# ehomeShades_doit_v2.net
KiCad netlist of a schematic drawn in EAGLE
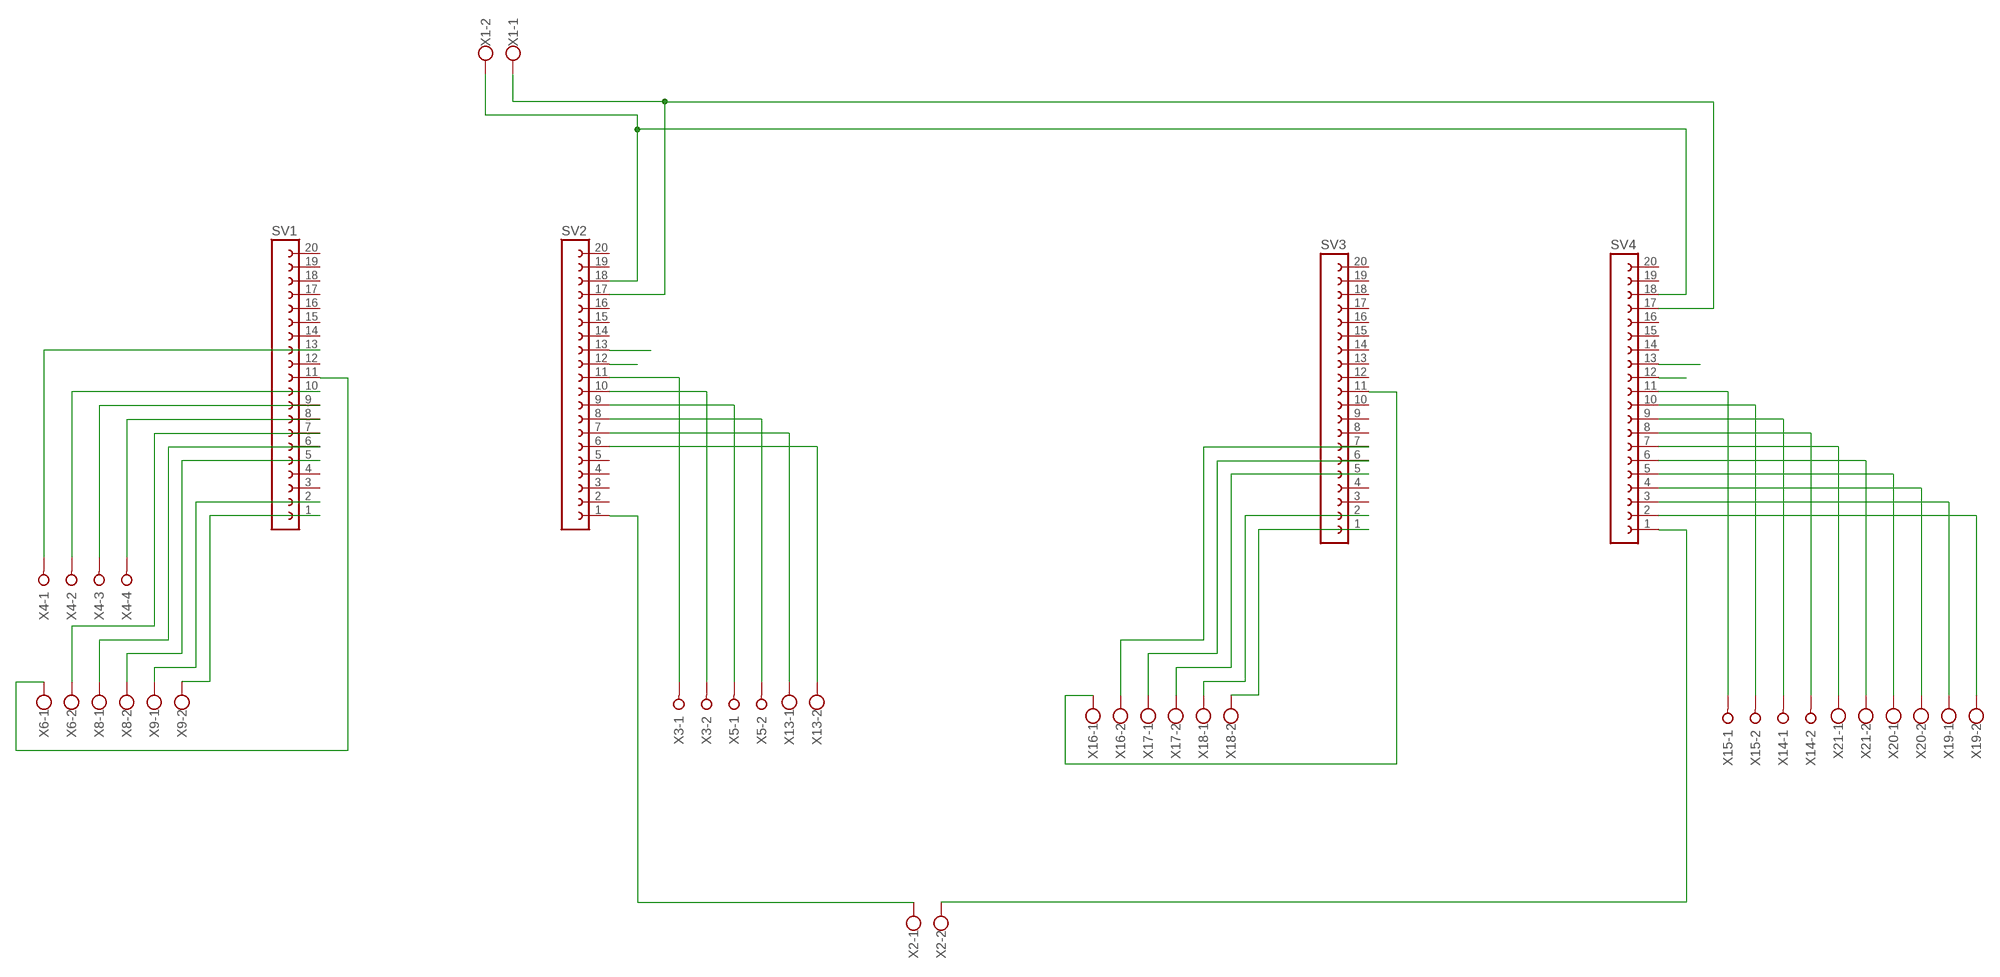
[diagram p0: schematic, sheet 1]

(export (version "E")
  (design (tool "Eeschema 10.0.6"))
  (components
    (comp (ref "SV1")
      (value "FE20-1")
      (footprint "eagle-import:FE20")
      (libsource (lib "eagle-import") (part "FE20-1"))
    )
    (comp (ref "SV2")
      (value "FE20-1")
      (footprint "eagle-import:FE20")
      (libsource (lib "eagle-import") (part "FE20-1"))
    )
    (comp (ref "SV3")
      (value "FE20-1")
      (footprint "eagle-import:FE20")
      (libsource (lib "eagle-import") (part "FE20-1"))
    )
    (comp (ref "SV4")
      (value "FE20-1")
      (footprint "eagle-import:FE20")
      (libsource (lib "eagle-import") (part "FE20-1"))
    )
    (comp (ref "X1")
      (value "W237-102")
      (footprint "eagle-import:W237-102")
      (fields (field (name "MPN") "237-102"))
      (libsource (lib "eagle-import") (part "W237-102"))
    )
    (comp (ref "X2")
      (value "W237-102")
      (footprint "eagle-import:W237-102")
      (fields (field (name "MPN") "237-102"))
      (libsource (lib "eagle-import") (part "W237-102"))
    )
    (comp (ref "X3")
      (value "W237-02P")
      (footprint "eagle-import:W237-132")
      (libsource (lib "eagle-import") (part "W237-02P"))
    )
    (comp (ref "X4")
      (value "W237-04P")
      (footprint "eagle-import:W237-4P")
      (libsource (lib "eagle-import") (part "W237-04P"))
    )
    (comp (ref "X5")
      (value "W237-02P")
      (footprint "eagle-import:W237-132")
      (libsource (lib "eagle-import") (part "W237-02P"))
    )
    (comp (ref "X6")
      (value "W237-102")
      (footprint "eagle-import:W237-102")
      (fields (field (name "MPN") "237-102"))
      (libsource (lib "eagle-import") (part "W237-102"))
    )
    (comp (ref "X8")
      (value "W237-102")
      (footprint "eagle-import:W237-102")
      (fields (field (name "MPN") "237-102"))
      (libsource (lib "eagle-import") (part "W237-102"))
    )
    (comp (ref "X9")
      (value "W237-102")
      (footprint "eagle-import:W237-102")
      (fields (field (name "MPN") "237-102"))
      (libsource (lib "eagle-import") (part "W237-102"))
    )
    (comp (ref "X13")
      (value "W237-102")
      (footprint "eagle-import:W237-102")
      (fields (field (name "MPN") "237-102"))
      (libsource (lib "eagle-import") (part "W237-102"))
    )
    (comp (ref "X14")
      (value "W237-02P")
      (footprint "eagle-import:W237-132")
      (libsource (lib "eagle-import") (part "W237-02P"))
    )
    (comp (ref "X15")
      (value "W237-02P")
      (footprint "eagle-import:W237-132")
      (libsource (lib "eagle-import") (part "W237-02P"))
    )
    (comp (ref "X16")
      (value "W237-102")
      (footprint "eagle-import:W237-102")
      (fields (field (name "MPN") "237-102"))
      (libsource (lib "eagle-import") (part "W237-102"))
    )
    (comp (ref "X17")
      (value "W237-102")
      (footprint "eagle-import:W237-102")
      (fields (field (name "MPN") "237-102"))
      (libsource (lib "eagle-import") (part "W237-102"))
    )
    (comp (ref "X18")
      (value "W237-102")
      (footprint "eagle-import:W237-102")
      (fields (field (name "MPN") "237-102"))
      (libsource (lib "eagle-import") (part "W237-102"))
    )
    (comp (ref "X19")
      (value "W237-102")
      (footprint "eagle-import:W237-102")
      (fields (field (name "MPN") "237-102"))
      (libsource (lib "eagle-import") (part "W237-102"))
    )
    (comp (ref "X20")
      (value "W237-102")
      (footprint "eagle-import:W237-102")
      (fields (field (name "MPN") "237-102"))
      (libsource (lib "eagle-import") (part "W237-102"))
    )
    (comp (ref "X21")
      (value "W237-102")
      (footprint "eagle-import:W237-102")
      (fields (field (name "MPN") "237-102"))
      (libsource (lib "eagle-import") (part "W237-102"))
    )
  )
  (nets
    (net (code "1") (name "Net-(X1A-KL)") (class "Default")
      (node (ref "SV2") (pin "17") (pinfunction "17_17") (pintype "passive"))
      (node (ref "SV4") (pin "17") (pinfunction "17_17") (pintype "passive"))
      (node (ref "X1") (pin "1") (pinfunction "KL_1") (pintype "passive"))
    )
    (net (code "2") (name "Net-(X1B-KL)") (class "Default")
      (node (ref "SV2") (pin "18") (pinfunction "18_18") (pintype "passive"))
      (node (ref "SV4") (pin "18") (pinfunction "18_18") (pintype "passive"))
      (node (ref "X1") (pin "2") (pinfunction "KL_2") (pintype "passive"))
    )
    (net (code "3") (name "Net-(X2A-KL)") (class "Default")
      (node (ref "SV2") (pin "1") (pinfunction "1_1") (pintype "passive"))
      (node (ref "X2") (pin "1") (pinfunction "KL_1") (pintype "passive"))
    )
    (net (code "4") (name "Net-(X2B-KL)") (class "Default")
      (node (ref "SV4") (pin "1") (pinfunction "1_1") (pintype "passive"))
      (node (ref "X2") (pin "2") (pinfunction "KL_2") (pintype "passive"))
    )
    (net (code "5") (name "Net-(X3A-KL)") (class "Default")
      (node (ref "SV2") (pin "11") (pinfunction "11_11") (pintype "passive"))
      (node (ref "X3") (pin "1") (pinfunction "KL_1") (pintype "passive"))
    )
    (net (code "6") (name "Net-(X3B-KL)") (class "Default")
      (node (ref "SV2") (pin "10") (pinfunction "10_10") (pintype "passive"))
      (node (ref "X3") (pin "2") (pinfunction "KL_2") (pintype "passive"))
    )
    (net (code "7") (name "Net-(X4A-KL)") (class "Default")
      (node (ref "SV1") (pin "13") (pinfunction "13_13") (pintype "passive"))
      (node (ref "X4") (pin "1") (pinfunction "KL_1") (pintype "passive"))
    )
    (net (code "8") (name "Net-(X4B-KL)") (class "Default")
      (node (ref "SV1") (pin "10") (pinfunction "10_10") (pintype "passive"))
      (node (ref "X4") (pin "2") (pinfunction "KL_2") (pintype "passive"))
    )
    (net (code "9") (name "Net-(X4C-KL)") (class "Default")
      (node (ref "SV1") (pin "9") (pinfunction "9_9") (pintype "passive"))
      (node (ref "X4") (pin "3") (pinfunction "KL_3") (pintype "passive"))
    )
    (net (code "10") (name "Net-(X4D-KL)") (class "Default")
      (node (ref "SV1") (pin "8") (pinfunction "8_8") (pintype "passive"))
      (node (ref "X4") (pin "4") (pinfunction "KL_4") (pintype "passive"))
    )
    (net (code "11") (name "Net-(X5A-KL)") (class "Default")
      (node (ref "SV2") (pin "9") (pinfunction "9_9") (pintype "passive"))
      (node (ref "X5") (pin "1") (pinfunction "KL_1") (pintype "passive"))
    )
    (net (code "12") (name "Net-(X5B-KL)") (class "Default")
      (node (ref "SV2") (pin "8") (pinfunction "8_8") (pintype "passive"))
      (node (ref "X5") (pin "2") (pinfunction "KL_2") (pintype "passive"))
    )
    (net (code "13") (name "Net-(X6A-KL)") (class "Default")
      (node (ref "SV1") (pin "11") (pinfunction "11_11") (pintype "passive"))
      (node (ref "X6") (pin "1") (pinfunction "KL_1") (pintype "passive"))
    )
    (net (code "14") (name "Net-(X6B-KL)") (class "Default")
      (node (ref "SV1") (pin "7") (pinfunction "7_7") (pintype "passive"))
      (node (ref "X6") (pin "2") (pinfunction "KL_2") (pintype "passive"))
    )
    (net (code "15") (name "Net-(X8A-KL)") (class "Default")
      (node (ref "SV1") (pin "6") (pinfunction "6_6") (pintype "passive"))
      (node (ref "X8") (pin "1") (pinfunction "KL_1") (pintype "passive"))
    )
    (net (code "16") (name "Net-(X8B-KL)") (class "Default")
      (node (ref "SV1") (pin "5") (pinfunction "5_5") (pintype "passive"))
      (node (ref "X8") (pin "2") (pinfunction "KL_2") (pintype "passive"))
    )
    (net (code "17") (name "Net-(X9A-KL)") (class "Default")
      (node (ref "SV1") (pin "2") (pinfunction "2_2") (pintype "passive"))
      (node (ref "X9") (pin "1") (pinfunction "KL_1") (pintype "passive"))
    )
    (net (code "18") (name "Net-(X9B-KL)") (class "Default")
      (node (ref "SV1") (pin "1") (pinfunction "1_1") (pintype "passive"))
      (node (ref "X9") (pin "2") (pinfunction "KL_2") (pintype "passive"))
    )
    (net (code "19") (name "Net-(X13A-KL)") (class "Default")
      (node (ref "SV2") (pin "7") (pinfunction "7_7") (pintype "passive"))
      (node (ref "X13") (pin "1") (pinfunction "KL_1") (pintype "passive"))
    )
    (net (code "20") (name "Net-(X13B-KL)") (class "Default")
      (node (ref "SV2") (pin "6") (pinfunction "6_6") (pintype "passive"))
      (node (ref "X13") (pin "2") (pinfunction "KL_2") (pintype "passive"))
    )
    (net (code "21") (name "Net-(X14A-KL)") (class "Default")
      (node (ref "SV4") (pin "9") (pinfunction "9_9") (pintype "passive"))
      (node (ref "X14") (pin "1") (pinfunction "KL_1") (pintype "passive"))
    )
    (net (code "22") (name "Net-(X14B-KL)") (class "Default")
      (node (ref "SV4") (pin "8") (pinfunction "8_8") (pintype "passive"))
      (node (ref "X14") (pin "2") (pinfunction "KL_2") (pintype "passive"))
    )
    (net (code "23") (name "Net-(X15A-KL)") (class "Default")
      (node (ref "SV4") (pin "11") (pinfunction "11_11") (pintype "passive"))
      (node (ref "X15") (pin "1") (pinfunction "KL_1") (pintype "passive"))
    )
    (net (code "24") (name "Net-(X15B-KL)") (class "Default")
      (node (ref "SV4") (pin "10") (pinfunction "10_10") (pintype "passive"))
      (node (ref "X15") (pin "2") (pinfunction "KL_2") (pintype "passive"))
    )
    (net (code "25") (name "Net-(X16A-KL)") (class "Default")
      (node (ref "SV3") (pin "11") (pinfunction "11_11") (pintype "passive"))
      (node (ref "X16") (pin "1") (pinfunction "KL_1") (pintype "passive"))
    )
    (net (code "26") (name "Net-(X16B-KL)") (class "Default")
      (node (ref "SV3") (pin "7") (pinfunction "7_7") (pintype "passive"))
      (node (ref "X16") (pin "2") (pinfunction "KL_2") (pintype "passive"))
    )
    (net (code "27") (name "Net-(X17A-KL)") (class "Default")
      (node (ref "SV3") (pin "6") (pinfunction "6_6") (pintype "passive"))
      (node (ref "X17") (pin "1") (pinfunction "KL_1") (pintype "passive"))
    )
    (net (code "28") (name "Net-(X17B-KL)") (class "Default")
      (node (ref "SV3") (pin "5") (pinfunction "5_5") (pintype "passive"))
      (node (ref "X17") (pin "2") (pinfunction "KL_2") (pintype "passive"))
    )
    (net (code "29") (name "Net-(X18A-KL)") (class "Default")
      (node (ref "SV3") (pin "2") (pinfunction "2_2") (pintype "passive"))
      (node (ref "X18") (pin "1") (pinfunction "KL_1") (pintype "passive"))
    )
    (net (code "30") (name "Net-(X18B-KL)") (class "Default")
      (node (ref "SV3") (pin "1") (pinfunction "1_1") (pintype "passive"))
      (node (ref "X18") (pin "2") (pinfunction "KL_2") (pintype "passive"))
    )
    (net (code "31") (name "Net-(X19A-KL)") (class "Default")
      (node (ref "SV4") (pin "3") (pinfunction "3_3") (pintype "passive"))
      (node (ref "X19") (pin "1") (pinfunction "KL_1") (pintype "passive"))
    )
    (net (code "32") (name "Net-(X19B-KL)") (class "Default")
      (node (ref "SV4") (pin "2") (pinfunction "2_2") (pintype "passive"))
      (node (ref "X19") (pin "2") (pinfunction "KL_2") (pintype "passive"))
    )
    (net (code "33") (name "Net-(X20A-KL)") (class "Default")
      (node (ref "SV4") (pin "5") (pinfunction "5_5") (pintype "passive"))
      (node (ref "X20") (pin "1") (pinfunction "KL_1") (pintype "passive"))
    )
    (net (code "34") (name "Net-(X20B-KL)") (class "Default")
      (node (ref "SV4") (pin "4") (pinfunction "4_4") (pintype "passive"))
      (node (ref "X20") (pin "2") (pinfunction "KL_2") (pintype "passive"))
    )
    (net (code "35") (name "Net-(X21A-KL)") (class "Default")
      (node (ref "SV4") (pin "7") (pinfunction "7_7") (pintype "passive"))
      (node (ref "X21") (pin "1") (pinfunction "KL_1") (pintype "passive"))
    )
    (net (code "36") (name "Net-(X21B-KL)") (class "Default")
      (node (ref "SV4") (pin "6") (pinfunction "6_6") (pintype "passive"))
      (node (ref "X21") (pin "2") (pinfunction "KL_2") (pintype "passive"))
    )
    (net (code "37") (name "unconnected-(SV1-Pad3)") (class "Default")
      (node (ref "SV1") (pin "3") (pinfunction "3_3") (pintype "passive"))
    )
    (net (code "38") (name "unconnected-(SV1-Pad4)") (class "Default")
      (node (ref "SV1") (pin "4") (pinfunction "4_4") (pintype "passive"))
    )
    (net (code "39") (name "unconnected-(SV1-Pad12)") (class "Default")
      (node (ref "SV1") (pin "12") (pinfunction "12_12") (pintype "passive"))
    )
    (net (code "40") (name "unconnected-(SV1-Pad14)") (class "Default")
      (node (ref "SV1") (pin "14") (pinfunction "14_14") (pintype "passive"))
    )
    (net (code "41") (name "unconnected-(SV1-Pad15)") (class "Default")
      (node (ref "SV1") (pin "15") (pinfunction "15_15") (pintype "passive"))
    )
    (net (code "42") (name "unconnected-(SV1-Pad16)") (class "Default")
      (node (ref "SV1") (pin "16") (pinfunction "16_16") (pintype "passive"))
    )
    (net (code "43") (name "unconnected-(SV1-Pad17)") (class "Default")
      (node (ref "SV1") (pin "17") (pinfunction "17_17") (pintype "passive"))
    )
    (net (code "44") (name "unconnected-(SV1-Pad18)") (class "Default")
      (node (ref "SV1") (pin "18") (pinfunction "18_18") (pintype "passive"))
    )
    (net (code "45") (name "unconnected-(SV1-Pad19)") (class "Default")
      (node (ref "SV1") (pin "19") (pinfunction "19_19") (pintype "passive"))
    )
    (net (code "46") (name "unconnected-(SV1-Pad20)") (class "Default")
      (node (ref "SV1") (pin "20") (pinfunction "20_20") (pintype "passive"))
    )
    (net (code "47") (name "unconnected-(SV2-Pad2)") (class "Default")
      (node (ref "SV2") (pin "2") (pinfunction "2_2") (pintype "passive"))
    )
    (net (code "48") (name "unconnected-(SV2-Pad3)") (class "Default")
      (node (ref "SV2") (pin "3") (pinfunction "3_3") (pintype "passive"))
    )
    (net (code "49") (name "unconnected-(SV2-Pad4)") (class "Default")
      (node (ref "SV2") (pin "4") (pinfunction "4_4") (pintype "passive"))
    )
    (net (code "50") (name "unconnected-(SV2-Pad5)") (class "Default")
      (node (ref "SV2") (pin "5") (pinfunction "5_5") (pintype "passive"))
    )
    (net (code "51") (name "unconnected-(SV2-Pad12)") (class "Default")
      (node (ref "SV2") (pin "12") (pinfunction "12_12") (pintype "passive"))
    )
    (net (code "52") (name "unconnected-(SV2-Pad13)") (class "Default")
      (node (ref "SV2") (pin "13") (pinfunction "13_13") (pintype "passive"))
    )
    (net (code "53") (name "unconnected-(SV2-Pad14)") (class "Default")
      (node (ref "SV2") (pin "14") (pinfunction "14_14") (pintype "passive"))
    )
    (net (code "54") (name "unconnected-(SV2-Pad15)") (class "Default")
      (node (ref "SV2") (pin "15") (pinfunction "15_15") (pintype "passive"))
    )
    (net (code "55") (name "unconnected-(SV2-Pad16)") (class "Default")
      (node (ref "SV2") (pin "16") (pinfunction "16_16") (pintype "passive"))
    )
    (net (code "56") (name "unconnected-(SV2-Pad19)") (class "Default")
      (node (ref "SV2") (pin "19") (pinfunction "19_19") (pintype "passive"))
    )
    (net (code "57") (name "unconnected-(SV2-Pad20)") (class "Default")
      (node (ref "SV2") (pin "20") (pinfunction "20_20") (pintype "passive"))
    )
    (net (code "58") (name "unconnected-(SV3-Pad3)") (class "Default")
      (node (ref "SV3") (pin "3") (pinfunction "3_3") (pintype "passive"))
    )
    (net (code "59") (name "unconnected-(SV3-Pad4)") (class "Default")
      (node (ref "SV3") (pin "4") (pinfunction "4_4") (pintype "passive"))
    )
    (net (code "60") (name "unconnected-(SV3-Pad8)") (class "Default")
      (node (ref "SV3") (pin "8") (pinfunction "8_8") (pintype "passive"))
    )
    (net (code "61") (name "unconnected-(SV3-Pad9)") (class "Default")
      (node (ref "SV3") (pin "9") (pinfunction "9_9") (pintype "passive"))
    )
    (net (code "62") (name "unconnected-(SV3-Pad10)") (class "Default")
      (node (ref "SV3") (pin "10") (pinfunction "10_10") (pintype "passive"))
    )
    (net (code "63") (name "unconnected-(SV3-Pad12)") (class "Default")
      (node (ref "SV3") (pin "12") (pinfunction "12_12") (pintype "passive"))
    )
    (net (code "64") (name "unconnected-(SV3-Pad13)") (class "Default")
      (node (ref "SV3") (pin "13") (pinfunction "13_13") (pintype "passive"))
    )
    (net (code "65") (name "unconnected-(SV3-Pad14)") (class "Default")
      (node (ref "SV3") (pin "14") (pinfunction "14_14") (pintype "passive"))
    )
    (net (code "66") (name "unconnected-(SV3-Pad15)") (class "Default")
      (node (ref "SV3") (pin "15") (pinfunction "15_15") (pintype "passive"))
    )
    (net (code "67") (name "unconnected-(SV3-Pad16)") (class "Default")
      (node (ref "SV3") (pin "16") (pinfunction "16_16") (pintype "passive"))
    )
    (net (code "68") (name "unconnected-(SV3-Pad17)") (class "Default")
      (node (ref "SV3") (pin "17") (pinfunction "17_17") (pintype "passive"))
    )
    (net (code "69") (name "unconnected-(SV3-Pad18)") (class "Default")
      (node (ref "SV3") (pin "18") (pinfunction "18_18") (pintype "passive"))
    )
    (net (code "70") (name "unconnected-(SV3-Pad19)") (class "Default")
      (node (ref "SV3") (pin "19") (pinfunction "19_19") (pintype "passive"))
    )
    (net (code "71") (name "unconnected-(SV3-Pad20)") (class "Default")
      (node (ref "SV3") (pin "20") (pinfunction "20_20") (pintype "passive"))
    )
    (net (code "72") (name "unconnected-(SV4-Pad12)") (class "Default")
      (node (ref "SV4") (pin "12") (pinfunction "12_12") (pintype "passive"))
    )
    (net (code "73") (name "unconnected-(SV4-Pad13)") (class "Default")
      (node (ref "SV4") (pin "13") (pinfunction "13_13") (pintype "passive"))
    )
    (net (code "74") (name "unconnected-(SV4-Pad14)") (class "Default")
      (node (ref "SV4") (pin "14") (pinfunction "14_14") (pintype "passive"))
    )
    (net (code "75") (name "unconnected-(SV4-Pad15)") (class "Default")
      (node (ref "SV4") (pin "15") (pinfunction "15_15") (pintype "passive"))
    )
    (net (code "76") (name "unconnected-(SV4-Pad16)") (class "Default")
      (node (ref "SV4") (pin "16") (pinfunction "16_16") (pintype "passive"))
    )
    (net (code "77") (name "unconnected-(SV4-Pad19)") (class "Default")
      (node (ref "SV4") (pin "19") (pinfunction "19_19") (pintype "passive"))
    )
    (net (code "78") (name "unconnected-(SV4-Pad20)") (class "Default")
      (node (ref "SV4") (pin "20") (pinfunction "20_20") (pintype "passive"))
    )
  )
)
